# lab2h.net
KiCad netlist of a schematic drawn in EAGLE
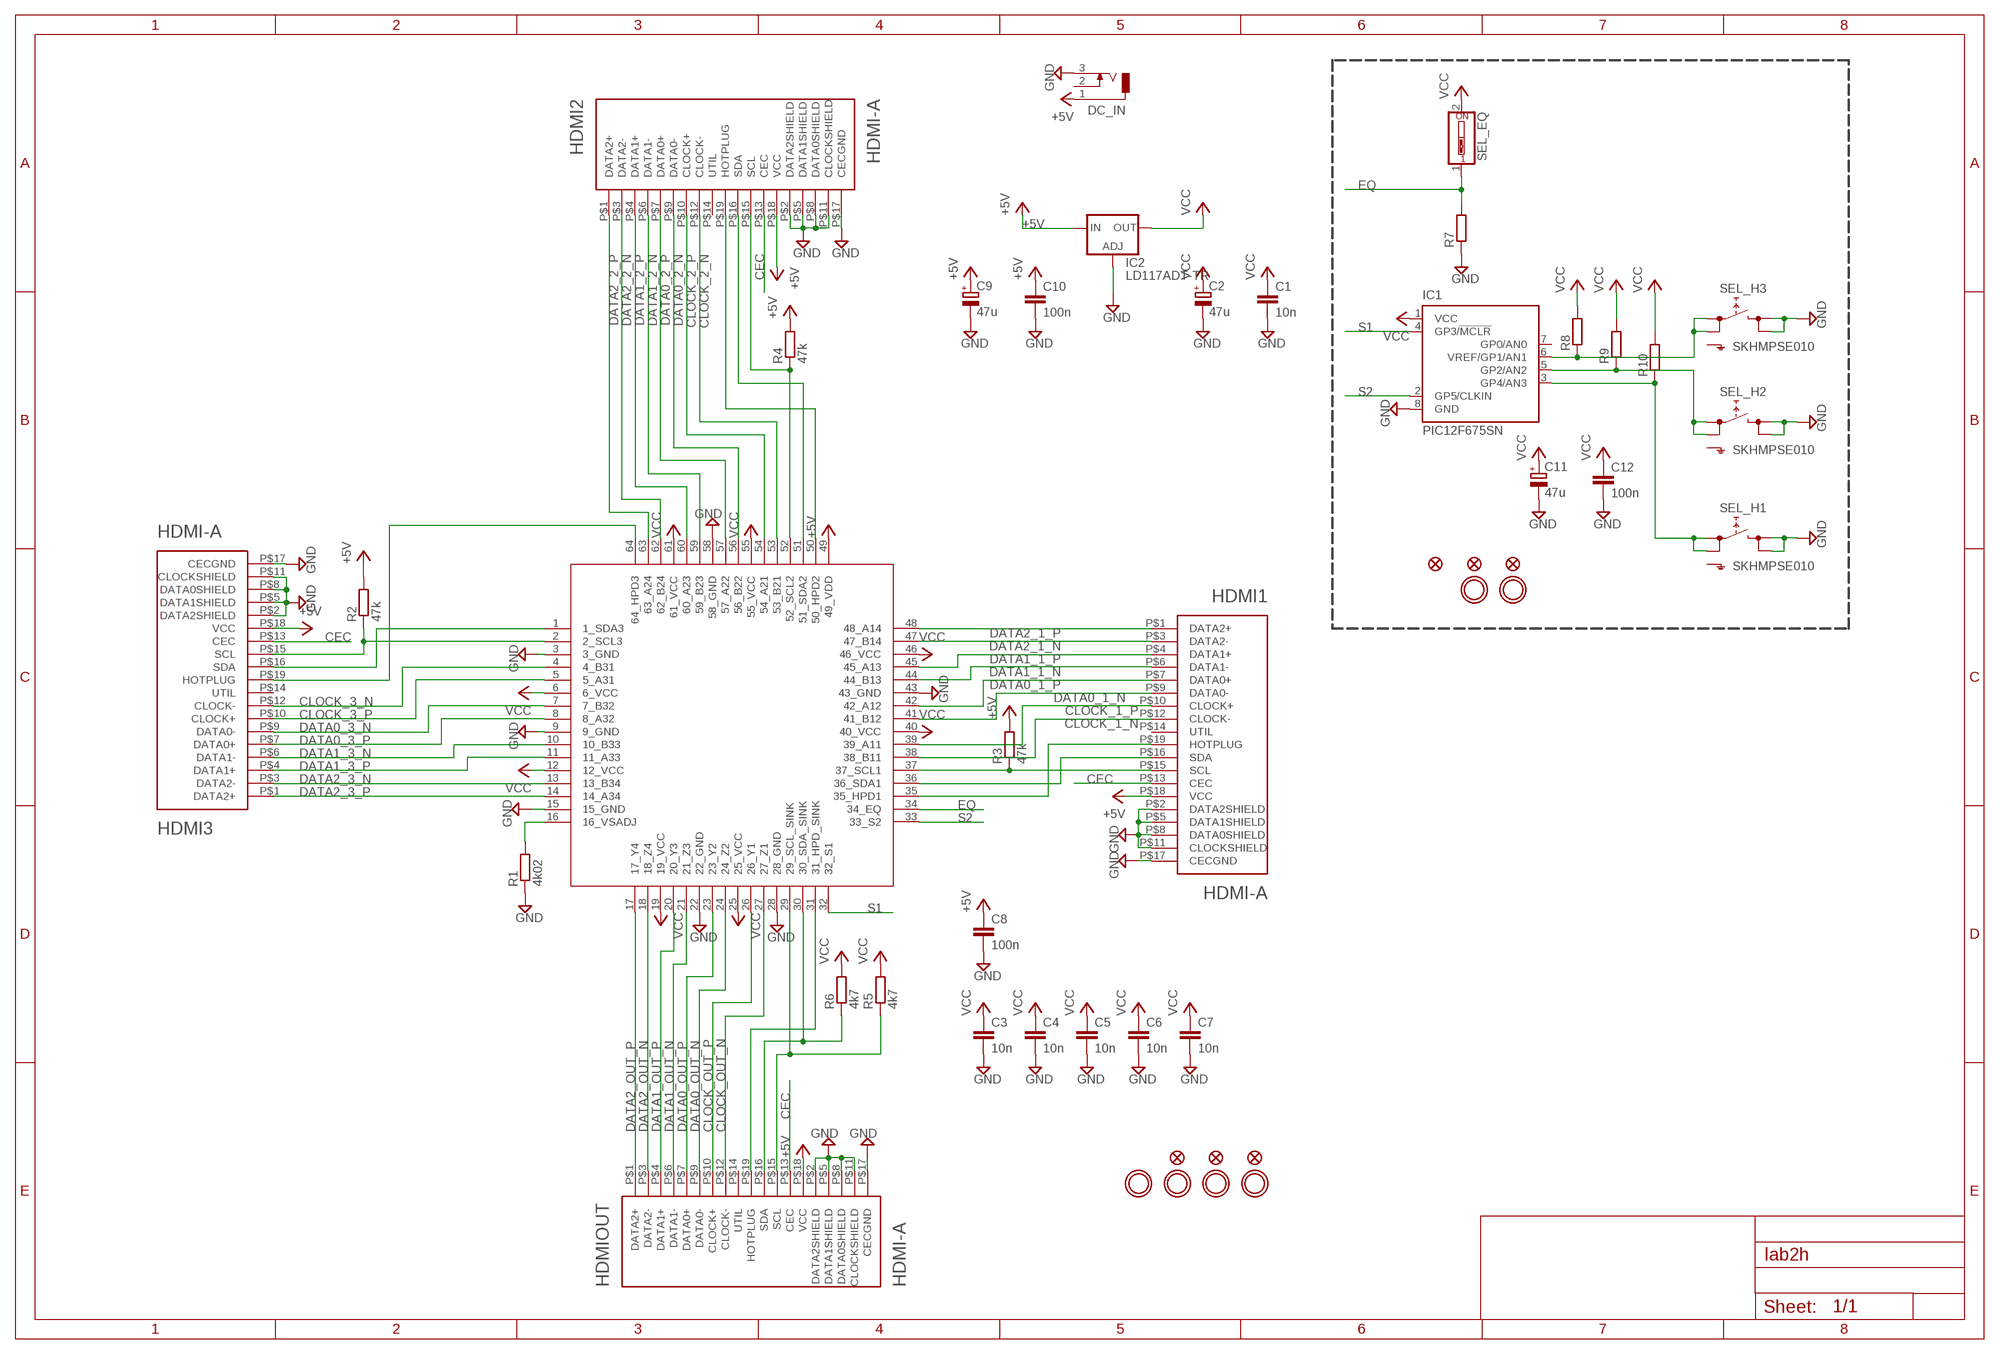
[diagram p0: schematic, sheet 1]

(export (version "E")
  (design (tool "Eeschema 10.0.6"))
  (components
    (comp (ref "C1")
      (value "10n")
      (footprint "eagle-import:C0402")
      (libsource (lib "eagle-import") (part "C-EUC0402"))
    )
    (comp (ref "C2")
      (value "47u")
      (footprint "eagle-import:SMC_A")
      (libsource (lib "eagle-import") (part "CPOL-EUSMCA"))
    )
    (comp (ref "C3")
      (value "10n")
      (footprint "eagle-import:0402")
      (libsource (lib "eagle-import") (part "C0402"))
    )
    (comp (ref "C4")
      (value "10n")
      (footprint "eagle-import:0402")
      (libsource (lib "eagle-import") (part "C0402"))
    )
    (comp (ref "C5")
      (value "10n")
      (footprint "eagle-import:0402")
      (libsource (lib "eagle-import") (part "C0402"))
    )
    (comp (ref "C6")
      (value "10n")
      (footprint "eagle-import:0402")
      (libsource (lib "eagle-import") (part "C0402"))
    )
    (comp (ref "C7")
      (value "10n")
      (footprint "eagle-import:0402")
      (libsource (lib "eagle-import") (part "C0402"))
    )
    (comp (ref "C8")
      (value "100n")
      (footprint "eagle-import:0402")
      (libsource (lib "eagle-import") (part "C0402"))
    )
    (comp (ref "C9")
      (value "47u")
      (footprint "eagle-import:SMC_A")
      (libsource (lib "eagle-import") (part "CPOL-EUSMCA"))
    )
    (comp (ref "C10")
      (value "100n")
      (footprint "eagle-import:C0402")
      (libsource (lib "eagle-import") (part "C-EUC0402"))
    )
    (comp (ref "C11")
      (value "47u")
      (footprint "eagle-import:SMC_A")
      (libsource (lib "eagle-import") (part "CPOL-EUSMCA"))
    )
    (comp (ref "C12")
      (value "100n")
      (footprint "eagle-import:C0402")
      (libsource (lib "eagle-import") (part "C-EUC0402"))
    )
    (comp (ref "DC_IN")
      (value "DCJ0303")
      (footprint "eagle-import:DCJ0303")
      (libsource (lib "eagle-import") (part "DCJ0303"))
    )
    (comp (ref "FID1")
      (value "FIDUCIAL\"\"")
      (footprint "eagle-import:FIDUCIAL_1MM")
      (libsource (lib "eagle-import") (part "FIDUCIAL{dblquote}{dblquote}"))
    )
    (comp (ref "FID2")
      (value "FIDUCIAL\"\"")
      (footprint "eagle-import:FIDUCIAL_1MM")
      (libsource (lib "eagle-import") (part "FIDUCIAL{dblquote}{dblquote}"))
    )
    (comp (ref "FID3")
      (value "FIDUCIAL\"\"")
      (footprint "eagle-import:FIDUCIAL_1MM")
      (libsource (lib "eagle-import") (part "FIDUCIAL{dblquote}{dblquote}"))
    )
    (comp (ref "FID4")
      (value "FIDUCIAL\"\"")
      (footprint "eagle-import:FIDUCIAL_1MM")
      (libsource (lib "eagle-import") (part "FIDUCIAL{dblquote}{dblquote}"))
    )
    (comp (ref "FID5")
      (value "FIDUCIAL\"\"")
      (footprint "eagle-import:FIDUCIAL_1MM")
      (libsource (lib "eagle-import") (part "FIDUCIAL{dblquote}{dblquote}"))
    )
    (comp (ref "FID6")
      (value "FIDUCIAL\"\"")
      (footprint "eagle-import:FIDUCIAL_1MM")
      (libsource (lib "eagle-import") (part "FIDUCIAL{dblquote}{dblquote}"))
    )
    (comp (ref "HDMI1")
      (value "HDMI-A")
      (footprint "eagle-import:HDMI_A")
      (libsource (lib "eagle-import") (part "HDMI-A"))
    )
    (comp (ref "HDMI2")
      (value "HDMI-A")
      (footprint "eagle-import:HDMI_A")
      (libsource (lib "eagle-import") (part "HDMI-A"))
    )
    (comp (ref "HDMI3")
      (value "HDMI-A")
      (footprint "eagle-import:HDMI_A")
      (libsource (lib "eagle-import") (part "HDMI-A"))
    )
    (comp (ref "HDMIOUT")
      (value "HDMI-A")
      (footprint "eagle-import:HDMI_A")
      (libsource (lib "eagle-import") (part "HDMI-A"))
    )
    (comp (ref "IC1")
      (value "PIC12F675SN")
      (footprint "eagle-import:SO-08")
      (fields (field (name "MF") "MICROCHIP") (field (name "MPN") "PIC12F675-E/SN"))
      (libsource (lib "eagle-import") (part "PIC12F675SN"))
    )
    (comp (ref "IC2")
      (value "LD117ADT-TR")
      (footprint "eagle-import:DPACK")
      (libsource (lib "eagle-import") (part "LD117A?DT-TR"))
    )
    (comp (ref "R1")
      (value "4k02")
      (footprint "eagle-import:0402")
      (libsource (lib "eagle-import") (part "R0402"))
    )
    (comp (ref "R2")
      (value "47k")
      (footprint "eagle-import:0402")
      (libsource (lib "eagle-import") (part "R0402"))
    )
    (comp (ref "R3")
      (value "47k")
      (footprint "eagle-import:0402")
      (libsource (lib "eagle-import") (part "R0402"))
    )
    (comp (ref "R4")
      (value "47k")
      (footprint "eagle-import:0402")
      (libsource (lib "eagle-import") (part "R0402"))
    )
    (comp (ref "R5")
      (value "4k7")
      (footprint "eagle-import:0402")
      (libsource (lib "eagle-import") (part "R0402"))
    )
    (comp (ref "R6")
      (value "4k7")
      (footprint "eagle-import:0402")
      (libsource (lib "eagle-import") (part "R0402"))
    )
    (comp (ref "R7")
      (value "R-EU_R0805")
      (footprint "eagle-import:R0805")
      (libsource (lib "eagle-import") (part "R-EU_R0805"))
    )
    (comp (ref "R8")
      (value "R-EU_R0805")
      (footprint "eagle-import:R0805")
      (libsource (lib "eagle-import") (part "R-EU_R0805"))
    )
    (comp (ref "R9")
      (value "R-EU_R0805")
      (footprint "eagle-import:R0805")
      (libsource (lib "eagle-import") (part "R-EU_R0805"))
    )
    (comp (ref "R10")
      (value "R-EU_R0805")
      (footprint "eagle-import:R0805")
      (libsource (lib "eagle-import") (part "R-EU_R0805"))
    )
    (comp (ref "SEL_EQ")
      (value "SW_DIP-1")
      (footprint "eagle-import:EDG-01")
      (libsource (lib "eagle-import") (part "SW_DIP-1"))
    )
    (comp (ref "SEL_H1")
      (value "SKHMPSE010")
      (footprint "eagle-import:SKHMPXE010")
      (libsource (lib "eagle-import") (part "SKHMPE010S"))
    )
    (comp (ref "SEL_H2")
      (value "SKHMPSE010")
      (footprint "eagle-import:SKHMPXE010")
      (libsource (lib "eagle-import") (part "SKHMPE010S"))
    )
    (comp (ref "SEL_H3")
      (value "SKHMPSE010")
      (footprint "eagle-import:SKHMPXE010")
      (libsource (lib "eagle-import") (part "SKHMPE010S"))
    )
    (comp (ref "U$1")
      (value "MOUNTINGHOLE3.0")
      (footprint "eagle-import:MOUNTINGHOLE_3.0_PLATED")
      (libsource (lib "eagle-import") (part "MOUNTINGHOLE3.0"))
    )
    (comp (ref "U$2")
      (value "MOUNTINGHOLE3.0")
      (footprint "eagle-import:MOUNTINGHOLE_3.0_PLATED")
      (libsource (lib "eagle-import") (part "MOUNTINGHOLE3.0"))
    )
    (comp (ref "U$31")
      (value "MOUNTINGHOLE3.0")
      (footprint "eagle-import:MOUNTINGHOLE_3.0_PLATED")
      (libsource (lib "eagle-import") (part "MOUNTINGHOLE3.0"))
    )
    (comp (ref "U$32")
      (value "MOUNTINGHOLE3.0")
      (footprint "eagle-import:MOUNTINGHOLE_3.0_PLATED")
      (libsource (lib "eagle-import") (part "MOUNTINGHOLE3.0"))
    )
    (comp (ref "U$33")
      (value "MOUNTINGHOLE3.0")
      (footprint "eagle-import:MOUNTINGHOLE_3.0_PLATED")
      (libsource (lib "eagle-import") (part "MOUNTINGHOLE3.0"))
    )
    (comp (ref "U$34")
      (value "MOUNTINGHOLE3.0")
      (footprint "eagle-import:MOUNTINGHOLE_3.0_PLATED")
      (libsource (lib "eagle-import") (part "MOUNTINGHOLE3.0"))
    )
    (comp (ref "U1")
      (value "TMDS351TQFP64")
      (footprint "eagle-import:QFP50P1200X1200X120-64")
      (libsource (lib "eagle-import") (part "TMDS351TQFP64"))
    )
  )
  (nets
    (net (code "1") (name "+5V") (class "Default")
      (node (ref "C10") (pin "1") (pinfunction "1_1") (pintype "passive"))
      (node (ref "C8") (pin "1") (pinfunction "1_1") (pintype "passive"))
      (node (ref "C9") (pin "+") (pinfunction "+_+") (pintype "passive"))
      (node (ref "DC_IN") (pin "1") (pinfunction "1_1") (pintype "passive"))
      (node (ref "HDMI1") (pin "P$18") (pinfunction "VCC_P$18") (pintype "bidirectional"))
      (node (ref "HDMI2") (pin "P$18") (pinfunction "VCC_P$18") (pintype "bidirectional"))
      (node (ref "HDMI3") (pin "P$18") (pinfunction "VCC_P$18") (pintype "bidirectional"))
      (node (ref "HDMIOUT") (pin "P$18") (pinfunction "VCC_P$18") (pintype "bidirectional"))
      (node (ref "IC2") (pin "3") (pinfunction "IN_3") (pintype "input"))
      (node (ref "R2") (pin "2") (pinfunction "2_2") (pintype "passive"))
      (node (ref "R3") (pin "2") (pinfunction "2_2") (pintype "passive"))
      (node (ref "R4") (pin "2") (pinfunction "2_2") (pintype "passive"))
      (node (ref "U1") (pin "49") (pinfunction "49_VDD_49") (pintype "bidirectional"))
    )
    (net (code "2") (name "/CEC") (class "Default")
      (node (ref "HDMI1") (pin "P$13") (pinfunction "CEC_P$13") (pintype "bidirectional"))
      (node (ref "HDMI2") (pin "P$13") (pinfunction "CEC_P$13") (pintype "bidirectional"))
      (node (ref "HDMI3") (pin "P$13") (pinfunction "CEC_P$13") (pintype "bidirectional"))
      (node (ref "HDMIOUT") (pin "P$13") (pinfunction "CEC_P$13") (pintype "bidirectional"))
    )
    (net (code "3") (name "/CLOCK_1_N") (class "Default")
      (node (ref "HDMI1") (pin "P$12") (pinfunction "CLOCK-_P$12") (pintype "bidirectional"))
      (node (ref "U1") (pin "38") (pinfunction "38_B11_38") (pintype "bidirectional"))
    )
    (net (code "4") (name "/CLOCK_1_P") (class "Default")
      (node (ref "HDMI1") (pin "P$10") (pinfunction "CLOCK+_P$10") (pintype "bidirectional"))
      (node (ref "U1") (pin "39") (pinfunction "39_A11_39") (pintype "bidirectional"))
    )
    (net (code "5") (name "/CLOCK_2_N") (class "Default")
      (node (ref "HDMI2") (pin "P$12") (pinfunction "CLOCK-_P$12") (pintype "bidirectional"))
      (node (ref "U1") (pin "53") (pinfunction "53_B21_53") (pintype "bidirectional"))
    )
    (net (code "6") (name "/CLOCK_2_P") (class "Default")
      (node (ref "HDMI2") (pin "P$10") (pinfunction "CLOCK+_P$10") (pintype "bidirectional"))
      (node (ref "U1") (pin "54") (pinfunction "54_A21_54") (pintype "bidirectional"))
    )
    (net (code "7") (name "/CLOCK_3_N") (class "Default")
      (node (ref "HDMI3") (pin "P$12") (pinfunction "CLOCK-_P$12") (pintype "bidirectional"))
      (node (ref "U1") (pin "4") (pinfunction "4_B31_4") (pintype "bidirectional"))
    )
    (net (code "8") (name "/CLOCK_3_P") (class "Default")
      (node (ref "HDMI3") (pin "P$10") (pinfunction "CLOCK+_P$10") (pintype "bidirectional"))
      (node (ref "U1") (pin "5") (pinfunction "5_A31_5") (pintype "bidirectional"))
    )
    (net (code "9") (name "/CLOCK_OUT_N") (class "Default")
      (node (ref "HDMIOUT") (pin "P$12") (pinfunction "CLOCK-_P$12") (pintype "bidirectional"))
      (node (ref "U1") (pin "27") (pinfunction "27_Z1_27") (pintype "bidirectional"))
    )
    (net (code "10") (name "/CLOCK_OUT_P") (class "Default")
      (node (ref "HDMIOUT") (pin "P$10") (pinfunction "CLOCK+_P$10") (pintype "bidirectional"))
      (node (ref "U1") (pin "26") (pinfunction "26_Y1_26") (pintype "bidirectional"))
    )
    (net (code "11") (name "/DATA0_1_N") (class "Default")
      (node (ref "HDMI1") (pin "P$9") (pinfunction "DATA0-_P$9") (pintype "bidirectional"))
      (node (ref "U1") (pin "41") (pinfunction "41_B12_41") (pintype "bidirectional"))
    )
    (net (code "12") (name "/DATA0_1_P") (class "Default")
      (node (ref "HDMI1") (pin "P$7") (pinfunction "DATA0+_P$7") (pintype "bidirectional"))
      (node (ref "U1") (pin "42") (pinfunction "42_A12_42") (pintype "bidirectional"))
    )
    (net (code "13") (name "/DATA0_2_N") (class "Default")
      (node (ref "HDMI2") (pin "P$9") (pinfunction "DATA0-_P$9") (pintype "bidirectional"))
      (node (ref "U1") (pin "56") (pinfunction "56_B22_56") (pintype "bidirectional"))
    )
    (net (code "14") (name "/DATA0_2_P") (class "Default")
      (node (ref "HDMI2") (pin "P$7") (pinfunction "DATA0+_P$7") (pintype "bidirectional"))
      (node (ref "U1") (pin "57") (pinfunction "57_A22_57") (pintype "bidirectional"))
    )
    (net (code "15") (name "/DATA0_3_N") (class "Default")
      (node (ref "HDMI3") (pin "P$9") (pinfunction "DATA0-_P$9") (pintype "bidirectional"))
      (node (ref "U1") (pin "7") (pinfunction "7_B32_7") (pintype "bidirectional"))
    )
    (net (code "16") (name "/DATA0_3_P") (class "Default")
      (node (ref "HDMI3") (pin "P$7") (pinfunction "DATA0+_P$7") (pintype "bidirectional"))
      (node (ref "U1") (pin "8") (pinfunction "8_A32_8") (pintype "bidirectional"))
    )
    (net (code "17") (name "/DATA0_OUT_N") (class "Default")
      (node (ref "HDMIOUT") (pin "P$9") (pinfunction "DATA0-_P$9") (pintype "bidirectional"))
      (node (ref "U1") (pin "24") (pinfunction "24_Z2_24") (pintype "bidirectional"))
    )
    (net (code "18") (name "/DATA0_OUT_P") (class "Default")
      (node (ref "HDMIOUT") (pin "P$7") (pinfunction "DATA0+_P$7") (pintype "bidirectional"))
      (node (ref "U1") (pin "23") (pinfunction "23_Y2_23") (pintype "bidirectional"))
    )
    (net (code "19") (name "/DATA1_1_N") (class "Default")
      (node (ref "HDMI1") (pin "P$6") (pinfunction "DATA1-_P$6") (pintype "bidirectional"))
      (node (ref "U1") (pin "44") (pinfunction "44_B13_44") (pintype "bidirectional"))
    )
    (net (code "20") (name "/DATA1_1_P") (class "Default")
      (node (ref "HDMI1") (pin "P$4") (pinfunction "DATA1+_P$4") (pintype "bidirectional"))
      (node (ref "U1") (pin "45") (pinfunction "45_A13_45") (pintype "bidirectional"))
    )
    (net (code "21") (name "/DATA1_2_N") (class "Default")
      (node (ref "HDMI2") (pin "P$6") (pinfunction "DATA1-_P$6") (pintype "bidirectional"))
      (node (ref "U1") (pin "59") (pinfunction "59_B23_59") (pintype "bidirectional"))
    )
    (net (code "22") (name "/DATA1_2_P") (class "Default")
      (node (ref "HDMI2") (pin "P$4") (pinfunction "DATA1+_P$4") (pintype "bidirectional"))
      (node (ref "U1") (pin "60") (pinfunction "60_A23_60") (pintype "bidirectional"))
    )
    (net (code "23") (name "/DATA1_3_N") (class "Default")
      (node (ref "HDMI3") (pin "P$6") (pinfunction "DATA1-_P$6") (pintype "bidirectional"))
      (node (ref "U1") (pin "10") (pinfunction "10_B33_10") (pintype "bidirectional"))
    )
    (net (code "24") (name "/DATA1_3_P") (class "Default")
      (node (ref "HDMI3") (pin "P$4") (pinfunction "DATA1+_P$4") (pintype "bidirectional"))
      (node (ref "U1") (pin "11") (pinfunction "11_A33_11") (pintype "bidirectional"))
    )
    (net (code "25") (name "/DATA1_OUT_N") (class "Default")
      (node (ref "HDMIOUT") (pin "P$6") (pinfunction "DATA1-_P$6") (pintype "bidirectional"))
      (node (ref "U1") (pin "21") (pinfunction "21_Z3_21") (pintype "bidirectional"))
    )
    (net (code "26") (name "/DATA1_OUT_P") (class "Default")
      (node (ref "HDMIOUT") (pin "P$4") (pinfunction "DATA1+_P$4") (pintype "bidirectional"))
      (node (ref "U1") (pin "20") (pinfunction "20_Y3_20") (pintype "bidirectional"))
    )
    (net (code "27") (name "/DATA2_1_N") (class "Default")
      (node (ref "HDMI1") (pin "P$3") (pinfunction "DATA2-_P$3") (pintype "bidirectional"))
      (node (ref "U1") (pin "47") (pinfunction "47_B14_47") (pintype "bidirectional"))
    )
    (net (code "28") (name "/DATA2_1_P") (class "Default")
      (node (ref "HDMI1") (pin "P$1") (pinfunction "DATA2+_P$1") (pintype "bidirectional"))
      (node (ref "U1") (pin "48") (pinfunction "48_A14_48") (pintype "bidirectional"))
    )
    (net (code "29") (name "/DATA2_2_N") (class "Default")
      (node (ref "HDMI2") (pin "P$3") (pinfunction "DATA2-_P$3") (pintype "bidirectional"))
      (node (ref "U1") (pin "62") (pinfunction "62_B24_62") (pintype "bidirectional"))
    )
    (net (code "30") (name "/DATA2_2_P") (class "Default")
      (node (ref "HDMI2") (pin "P$1") (pinfunction "DATA2+_P$1") (pintype "bidirectional"))
      (node (ref "U1") (pin "63") (pinfunction "63_A24_63") (pintype "bidirectional"))
    )
    (net (code "31") (name "/DATA2_3_N") (class "Default")
      (node (ref "HDMI3") (pin "P$3") (pinfunction "DATA2-_P$3") (pintype "bidirectional"))
      (node (ref "U1") (pin "13") (pinfunction "13_B34_13") (pintype "bidirectional"))
    )
    (net (code "32") (name "/DATA2_3_P") (class "Default")
      (node (ref "HDMI3") (pin "P$1") (pinfunction "DATA2+_P$1") (pintype "bidirectional"))
      (node (ref "U1") (pin "14") (pinfunction "14_A34_14") (pintype "bidirectional"))
    )
    (net (code "33") (name "/DATA2_OUT_N") (class "Default")
      (node (ref "HDMIOUT") (pin "P$3") (pinfunction "DATA2-_P$3") (pintype "bidirectional"))
      (node (ref "U1") (pin "18") (pinfunction "18_Z4_18") (pintype "bidirectional"))
    )
    (net (code "34") (name "/DATA2_OUT_P") (class "Default")
      (node (ref "HDMIOUT") (pin "P$1") (pinfunction "DATA2+_P$1") (pintype "bidirectional"))
      (node (ref "U1") (pin "17") (pinfunction "17_Y4_17") (pintype "bidirectional"))
    )
    (net (code "35") (name "/EQ") (class "Default")
      (node (ref "R7") (pin "2") (pinfunction "2_2") (pintype "passive"))
      (node (ref "SEL_EQ") (pin "1") (pinfunction "1_1") (pintype "passive"))
      (node (ref "U1") (pin "34") (pinfunction "34_EQ_34") (pintype "bidirectional"))
    )
    (net (code "36") (name "/S1") (class "Default")
      (node (ref "IC1") (pin "4") (pinfunction "GP3/~{MCLR}_4") (pintype "input"))
      (node (ref "U1") (pin "32") (pinfunction "32_S1_32") (pintype "bidirectional"))
    )
    (net (code "37") (name "/S2") (class "Default")
      (node (ref "IC1") (pin "2") (pinfunction "GP5/CLKIN_2") (pintype "bidirectional"))
      (node (ref "U1") (pin "33") (pinfunction "33_S2_33") (pintype "bidirectional"))
    )
    (net (code "38") (name "GND") (class "Default")
      (node (ref "C1") (pin "2") (pinfunction "2_2") (pintype "passive"))
      (node (ref "C10") (pin "2") (pinfunction "2_2") (pintype "passive"))
      (node (ref "C11") (pin "-") (pinfunction "-_-") (pintype "passive"))
      (node (ref "C12") (pin "2") (pinfunction "2_2") (pintype "passive"))
      (node (ref "C2") (pin "-") (pinfunction "-_-") (pintype "passive"))
      (node (ref "C3") (pin "2") (pinfunction "2_2") (pintype "passive"))
      (node (ref "C4") (pin "2") (pinfunction "2_2") (pintype "passive"))
      (node (ref "C5") (pin "2") (pinfunction "2_2") (pintype "passive"))
      (node (ref "C6") (pin "2") (pinfunction "2_2") (pintype "passive"))
      (node (ref "C7") (pin "2") (pinfunction "2_2") (pintype "passive"))
      (node (ref "C8") (pin "2") (pinfunction "2_2") (pintype "passive"))
      (node (ref "C9") (pin "-") (pinfunction "-_-") (pintype "passive"))
      (node (ref "DC_IN") (pin "3") (pinfunction "3_3") (pintype "passive"))
      (node (ref "HDMI1") (pin "P$11") (pinfunction "CLOCKSHIELD_P$11") (pintype "bidirectional"))
      (node (ref "HDMI1") (pin "P$17") (pinfunction "CECGND_P$17") (pintype "bidirectional"))
      (node (ref "HDMI1") (pin "P$2") (pinfunction "DATA2SHIELD_P$2") (pintype "bidirectional"))
      (node (ref "HDMI1") (pin "P$5") (pinfunction "DATA1SHIELD_P$5") (pintype "bidirectional"))
      (node (ref "HDMI1") (pin "P$8") (pinfunction "DATA0SHIELD_P$8") (pintype "bidirectional"))
      (node (ref "HDMI2") (pin "P$11") (pinfunction "CLOCKSHIELD_P$11") (pintype "bidirectional"))
      (node (ref "HDMI2") (pin "P$17") (pinfunction "CECGND_P$17") (pintype "bidirectional"))
      (node (ref "HDMI2") (pin "P$2") (pinfunction "DATA2SHIELD_P$2") (pintype "bidirectional"))
      (node (ref "HDMI2") (pin "P$5") (pinfunction "DATA1SHIELD_P$5") (pintype "bidirectional"))
      (node (ref "HDMI2") (pin "P$8") (pinfunction "DATA0SHIELD_P$8") (pintype "bidirectional"))
      (node (ref "HDMI3") (pin "P$11") (pinfunction "CLOCKSHIELD_P$11") (pintype "bidirectional"))
      (node (ref "HDMI3") (pin "P$17") (pinfunction "CECGND_P$17") (pintype "bidirectional"))
      (node (ref "HDMI3") (pin "P$2") (pinfunction "DATA2SHIELD_P$2") (pintype "bidirectional"))
      (node (ref "HDMI3") (pin "P$5") (pinfunction "DATA1SHIELD_P$5") (pintype "bidirectional"))
      (node (ref "HDMI3") (pin "P$8") (pinfunction "DATA0SHIELD_P$8") (pintype "bidirectional"))
      (node (ref "HDMIOUT") (pin "P$11") (pinfunction "CLOCKSHIELD_P$11") (pintype "bidirectional"))
      (node (ref "HDMIOUT") (pin "P$17") (pinfunction "CECGND_P$17") (pintype "bidirectional"))
      (node (ref "HDMIOUT") (pin "P$2") (pinfunction "DATA2SHIELD_P$2") (pintype "bidirectional"))
      (node (ref "HDMIOUT") (pin "P$5") (pinfunction "DATA1SHIELD_P$5") (pintype "bidirectional"))
      (node (ref "HDMIOUT") (pin "P$8") (pinfunction "DATA0SHIELD_P$8") (pintype "bidirectional"))
      (node (ref "IC1") (pin "8") (pinfunction "GND_8") (pintype "power_in"))
      (node (ref "IC2") (pin "1") (pinfunction "ADJ_1") (pintype "input"))
      (node (ref "R1") (pin "1") (pinfunction "1_1") (pintype "passive"))
      (node (ref "R7") (pin "1") (pinfunction "1_1") (pintype "passive"))
      (node (ref "SEL_H1") (pin "3") (pinfunction "2.1_3") (pintype "passive"))
      (node (ref "SEL_H1") (pin "4") (pinfunction "2.2_4") (pintype "passive"))
      (node (ref "SEL_H2") (pin "3") (pinfunction "2.1_3") (pintype "passive"))
      (node (ref "SEL_H2") (pin "4") (pinfunction "2.2_4") (pintype "passive"))
      (node (ref "SEL_H3") (pin "3") (pinfunction "2.1_3") (pintype "passive"))
      (node (ref "SEL_H3") (pin "4") (pinfunction "2.2_4") (pintype "passive"))
      (node (ref "U1") (pin "15") (pinfunction "15_GND_15") (pintype "bidirectional"))
      (node (ref "U1") (pin "22") (pinfunction "22_GND_22") (pintype "bidirectional"))
      (node (ref "U1") (pin "28") (pinfunction "28_GND_28") (pintype "bidirectional"))
      (node (ref "U1") (pin "3") (pinfunction "3_GND_3") (pintype "bidirectional"))
      (node (ref "U1") (pin "43") (pinfunction "43_GND_43") (pintype "bidirectional"))
      (node (ref "U1") (pin "58") (pinfunction "58_GND_58") (pintype "bidirectional"))
      (node (ref "U1") (pin "9") (pinfunction "9_GND_9") (pintype "bidirectional"))
    )
    (net (code "39") (name "Net-(HDMI1-HOTPLUG)") (class "Default")
      (node (ref "HDMI1") (pin "P$19") (pinfunction "HOTPLUG_P$19") (pintype "bidirectional"))
      (node (ref "U1") (pin "35") (pinfunction "35_HPD1_35") (pintype "bidirectional"))
    )
    (net (code "40") (name "Net-(HDMI1-SCL)") (class "Default")
      (node (ref "HDMI1") (pin "P$15") (pinfunction "SCL_P$15") (pintype "bidirectional"))
      (node (ref "R3") (pin "1") (pinfunction "1_1") (pintype "passive"))
      (node (ref "U1") (pin "37") (pinfunction "37_SCL1_37") (pintype "bidirectional"))
    )
    (net (code "41") (name "Net-(HDMI1-SDA)") (class "Default")
      (node (ref "HDMI1") (pin "P$16") (pinfunction "SDA_P$16") (pintype "bidirectional"))
      (node (ref "U1") (pin "36") (pinfunction "36_SDA1_36") (pintype "bidirectional"))
    )
    (net (code "42") (name "Net-(HDMI2-HOTPLUG)") (class "Default")
      (node (ref "HDMI2") (pin "P$19") (pinfunction "HOTPLUG_P$19") (pintype "bidirectional"))
      (node (ref "U1") (pin "50") (pinfunction "50_HPD2_50") (pintype "bidirectional"))
    )
    (net (code "43") (name "Net-(HDMI2-SCL)") (class "Default")
      (node (ref "HDMI2") (pin "P$15") (pinfunction "SCL_P$15") (pintype "bidirectional"))
      (node (ref "R4") (pin "1") (pinfunction "1_1") (pintype "passive"))
      (node (ref "U1") (pin "52") (pinfunction "52_SCL2_52") (pintype "bidirectional"))
    )
    (net (code "44") (name "Net-(HDMI2-SDA)") (class "Default")
      (node (ref "HDMI2") (pin "P$16") (pinfunction "SDA_P$16") (pintype "bidirectional"))
      (node (ref "U1") (pin "51") (pinfunction "51_SDA2_51") (pintype "bidirectional"))
    )
    (net (code "45") (name "Net-(HDMI3-HOTPLUG)") (class "Default")
      (node (ref "HDMI3") (pin "P$19") (pinfunction "HOTPLUG_P$19") (pintype "bidirectional"))
      (node (ref "U1") (pin "64") (pinfunction "64_HPD3_64") (pintype "bidirectional"))
    )
    (net (code "46") (name "Net-(HDMI3-SCL)") (class "Default")
      (node (ref "HDMI3") (pin "P$15") (pinfunction "SCL_P$15") (pintype "bidirectional"))
      (node (ref "R2") (pin "1") (pinfunction "1_1") (pintype "passive"))
      (node (ref "U1") (pin "2") (pinfunction "2_SCL3_2") (pintype "bidirectional"))
    )
    (net (code "47") (name "Net-(HDMI3-SDA)") (class "Default")
      (node (ref "HDMI3") (pin "P$16") (pinfunction "SDA_P$16") (pintype "bidirectional"))
      (node (ref "U1") (pin "1") (pinfunction "1_SDA3_1") (pintype "bidirectional"))
    )
    (net (code "48") (name "Net-(HDMIOUT-HOTPLUG)") (class "Default")
      (node (ref "HDMIOUT") (pin "P$19") (pinfunction "HOTPLUG_P$19") (pintype "bidirectional"))
      (node (ref "U1") (pin "31") (pinfunction "31_HPD_SINK_31") (pintype "bidirectional"))
    )
    (net (code "49") (name "Net-(HDMIOUT-SCL)") (class "Default")
      (node (ref "HDMIOUT") (pin "P$15") (pinfunction "SCL_P$15") (pintype "bidirectional"))
      (node (ref "R5") (pin "1") (pinfunction "1_1") (pintype "passive"))
      (node (ref "U1") (pin "29") (pinfunction "29_SCL_SINK_29") (pintype "bidirectional"))
    )
    (net (code "50") (name "Net-(HDMIOUT-SDA)") (class "Default")
      (node (ref "HDMIOUT") (pin "P$16") (pinfunction "SDA_P$16") (pintype "bidirectional"))
      (node (ref "R6") (pin "1") (pinfunction "1_1") (pintype "passive"))
      (node (ref "U1") (pin "30") (pinfunction "30_SDA_SINK_30") (pintype "bidirectional"))
    )
    (net (code "51") (name "Net-(IC1-GP2{slash}AN2)") (class "Default")
      (node (ref "IC1") (pin "5") (pinfunction "GP2/AN2_5") (pintype "bidirectional"))
      (node (ref "R9") (pin "1") (pinfunction "1_1") (pintype "passive"))
      (node (ref "SEL_H2") (pin "1") (pinfunction "1.1_1") (pintype "passive"))
      (node (ref "SEL_H2") (pin "2") (pinfunction "1.2_2") (pintype "passive"))
    )
    (net (code "52") (name "Net-(IC1-GP4{slash}AN3)") (class "Default")
      (node (ref "IC1") (pin "3") (pinfunction "GP4/AN3_3") (pintype "bidirectional"))
      (node (ref "R10") (pin "1") (pinfunction "1_1") (pintype "passive"))
      (node (ref "SEL_H1") (pin "1") (pinfunction "1.1_1") (pintype "passive"))
      (node (ref "SEL_H1") (pin "2") (pinfunction "1.2_2") (pintype "passive"))
    )
    (net (code "53") (name "Net-(IC1-VREF{slash}GP1{slash}AN1)") (class "Default")
      (node (ref "IC1") (pin "6") (pinfunction "VREF/GP1/AN1_6") (pintype "bidirectional"))
      (node (ref "R8") (pin "1") (pinfunction "1_1") (pintype "passive"))
      (node (ref "SEL_H3") (pin "1") (pinfunction "1.1_1") (pintype "passive"))
      (node (ref "SEL_H3") (pin "2") (pinfunction "1.2_2") (pintype "passive"))
    )
    (net (code "54") (name "Net-(U1-16_VSADJ)") (class "Default")
      (node (ref "R1") (pin "2") (pinfunction "2_2") (pintype "passive"))
      (node (ref "U1") (pin "16") (pinfunction "16_VSADJ_16") (pintype "bidirectional"))
    )
    (net (code "55") (name "VCC") (class "Default")
      (node (ref "C1") (pin "1") (pinfunction "1_1") (pintype "passive"))
      (node (ref "C11") (pin "+") (pinfunction "+_+") (pintype "passive"))
      (node (ref "C12") (pin "1") (pinfunction "1_1") (pintype "passive"))
      (node (ref "C2") (pin "+") (pinfunction "+_+") (pintype "passive"))
      (node (ref "C3") (pin "1") (pinfunction "1_1") (pintype "passive"))
      (node (ref "C4") (pin "1") (pinfunction "1_1") (pintype "passive"))
      (node (ref "C5") (pin "1") (pinfunction "1_1") (pintype "passive"))
      (node (ref "C6") (pin "1") (pinfunction "1_1") (pintype "passive"))
      (node (ref "C7") (pin "1") (pinfunction "1_1") (pintype "passive"))
      (node (ref "IC1") (pin "1") (pinfunction "VCC_1") (pintype "power_in"))
      (node (ref "IC2") (pin "4") (pinfunction "OUT_4") (pintype "passive"))
      (node (ref "R10") (pin "2") (pinfunction "2_2") (pintype "passive"))
      (node (ref "R5") (pin "2") (pinfunction "2_2") (pintype "passive"))
      (node (ref "R6") (pin "2") (pinfunction "2_2") (pintype "passive"))
      (node (ref "R8") (pin "2") (pinfunction "2_2") (pintype "passive"))
      (node (ref "R9") (pin "2") (pinfunction "2_2") (pintype "passive"))
      (node (ref "SEL_EQ") (pin "2") (pinfunction "2_2") (pintype "passive"))
      (node (ref "U1") (pin "12") (pinfunction "12_VCC_12") (pintype "bidirectional"))
      (node (ref "U1") (pin "19") (pinfunction "19_VCC_19") (pintype "bidirectional"))
      (node (ref "U1") (pin "25") (pinfunction "25_VCC_25") (pintype "bidirectional"))
      (node (ref "U1") (pin "40") (pinfunction "40_VCC_40") (pintype "bidirectional"))
      (node (ref "U1") (pin "46") (pinfunction "46_VCC_46") (pintype "bidirectional"))
      (node (ref "U1") (pin "55") (pinfunction "55_VCC_55") (pintype "bidirectional"))
      (node (ref "U1") (pin "6") (pinfunction "6_VCC_6") (pintype "bidirectional"))
      (node (ref "U1") (pin "61") (pinfunction "61_VCC_61") (pintype "bidirectional"))
    )
    (net (code "56") (name "unconnected-(DC_IN-Pad2)") (class "Default")
      (node (ref "DC_IN") (pin "2") (pinfunction "2_2") (pintype "passive"))
    )
    (net (code "57") (name "unconnected-(HDMI1-UTIL-PadP$14)") (class "Default")
      (node (ref "HDMI1") (pin "P$14") (pinfunction "UTIL_P$14") (pintype "bidirectional"))
    )
    (net (code "58") (name "unconnected-(HDMI2-UTIL-PadP$14)") (class "Default")
      (node (ref "HDMI2") (pin "P$14") (pinfunction "UTIL_P$14") (pintype "bidirectional"))
    )
    (net (code "59") (name "unconnected-(HDMI3-UTIL-PadP$14)") (class "Default")
      (node (ref "HDMI3") (pin "P$14") (pinfunction "UTIL_P$14") (pintype "bidirectional"))
    )
    (net (code "60") (name "unconnected-(HDMIOUT-UTIL-PadP$14)") (class "Default")
      (node (ref "HDMIOUT") (pin "P$14") (pinfunction "UTIL_P$14") (pintype "bidirectional"))
    )
    (net (code "61") (name "unconnected-(IC1-GP0{slash}AN0-Pad7)") (class "Default")
      (node (ref "IC1") (pin "7") (pinfunction "GP0/AN0_7") (pintype "bidirectional"))
    )
    (net (code "62") (name "unconnected-(SEL_H1-SH-Pad5)") (class "Default")
      (node (ref "SEL_H1") (pin "5") (pinfunction "SH_5") (pintype "passive"))
    )
    (net (code "63") (name "unconnected-(SEL_H2-SH-Pad5)") (class "Default")
      (node (ref "SEL_H2") (pin "5") (pinfunction "SH_5") (pintype "passive"))
    )
    (net (code "64") (name "unconnected-(SEL_H3-SH-Pad5)") (class "Default")
      (node (ref "SEL_H3") (pin "5") (pinfunction "SH_5") (pintype "passive"))
    )
  )
)
